# cSLIM-SA_display.net
KiCad netlist of a schematic drawn in Altium Designer
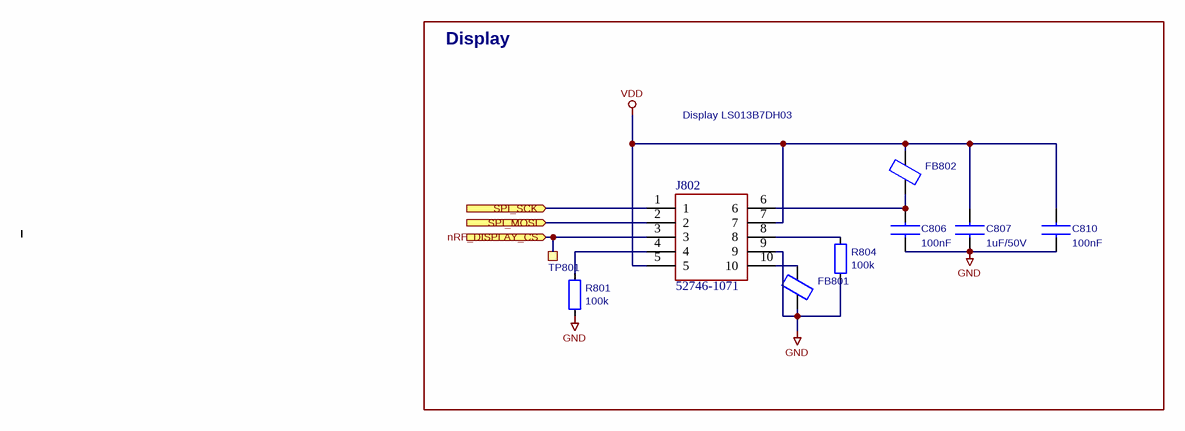
[diagram p0: cSLIM-SA_display.SchDoc]

(export (version "E")
  (design (tool "Eeschema 10.0.6"))
  (components
    (comp (ref "C806")
      (value "100nF")
      (footprint "cSLIM-SA:CAPC1608X90N")
      (description "Capacitor")
      (fields
        (field (name "MANUFACTURER_PART_NUMBER") "06033G104ZAT2A")
        (field (name "MOUSER PART NUMBER") "581-06033G104Z")
      )
      (libsource (lib "cSLIM-SA") (part "C"))
    )
    (comp (ref "C807")
      (value "1uF/50V")
      (footprint "cSLIM-SA:CAPC1608X90N")
      (description "Capacitor")
      (fields
        (field (name "MANUFACTURER_PART_NUMBER") "06033G104ZAT2A")
        (field (name "MOUSER PART NUMBER") "581-06033G104Z")
      )
      (libsource (lib "cSLIM-SA") (part "C"))
    )
    (comp (ref "C810")
      (value "100nF")
      (footprint "cSLIM-SA:CAPC1608X90N")
      (description "Capacitor")
      (fields
        (field (name "MANUFACTURER_PART_NUMBER") "06033G104ZAT2A")
        (field (name "MOUSER PART NUMBER") "581-06033G104Z")
      )
      (libsource (lib "cSLIM-SA") (part "C"))
    )
    (comp (ref "FB801")
      (value "Ferrite_Bead")
      (footprint "CAPC1608X90N")
      (libsource (lib "cSLIM-SA") (part "Ferrite_Bead"))
    )
    (comp (ref "FB802")
      (value "Ferrite_Bead")
      (footprint "CAPC1608X90N")
      (libsource (lib "cSLIM-SA") (part "Ferrite_Bead"))
    )
    (comp (ref "J802")
      (value "52746-1071")
      (footprint "cSLIM-SA:52746-1071")
      (description "Connector")
      (fields (field (name "MOUSER PART NUMBER") "538-52746-1071"))
      (libsource (lib "cSLIM-SA") (part "52746-1071"))
    )
    (comp (ref "R801") (value "100k") (footprint "RESC1608X55N") (libsource (lib "cSLIM-SA") (part "R")))
    (comp (ref "R804") (value "100k") (footprint "RESC1608X55N") (libsource (lib "cSLIM-SA") (part "R")))
    (comp (ref "TP801")
      (value "~")
      (footprint "cSLIM-SA:TP_SMD_Ø1.0mm")
      (libsource (lib "cSLIM-SA") (part "TP"))
    )
  )
  (nets
    (net (code "1") (name "/SPI_MOSI") (class "Default")
      (node (ref "J802") (pin "2") (pinfunction "2_2") (pintype "passive"))
    )
    (net (code "2") (name "/SPI_SCK") (class "Default")
      (node (ref "J802") (pin "1") (pinfunction "1_1") (pintype "passive"))
    )
    (net (code "3") (name "/nRF_DISPLAY_CS") (class "Default")
      (node (ref "J802") (pin "3") (pinfunction "3_3") (pintype "passive"))
      (node (ref "TP801") (pin "1") (pinfunction "1_1") (pintype "passive"))
    )
    (net (code "4") (name "GND") (class "Default")
      (node (ref "C806") (pin "2") (pinfunction "2_2") (pintype "passive"))
      (node (ref "C807") (pin "2") (pinfunction "2_2") (pintype "passive"))
      (node (ref "C810") (pin "2") (pinfunction "2_2") (pintype "passive"))
      (node (ref "FB801") (pin "2") (pinfunction "2_2") (pintype "passive"))
      (node (ref "J802") (pin "9") (pinfunction "9_9") (pintype "passive"))
      (node (ref "R801") (pin "2") (pinfunction "2_2") (pintype "passive"))
      (node (ref "R804") (pin "2") (pinfunction "2_2") (pintype "passive"))
    )
    (net (code "5") (name "Net-(C806-Pad1)") (class "Default")
      (node (ref "C806") (pin "1") (pinfunction "1_1") (pintype "passive"))
      (node (ref "FB802") (pin "2") (pinfunction "2_2") (pintype "passive"))
      (node (ref "J802") (pin "6") (pinfunction "6_6") (pintype "passive"))
    )
    (net (code "6") (name "Net-(FB801-Pad1)") (class "Default")
      (node (ref "FB801") (pin "1") (pinfunction "1_1") (pintype "passive"))
      (node (ref "J802") (pin "10") (pinfunction "10_10") (pintype "passive"))
    )
    (net (code "7") (name "Net-(J802-Pad4)") (class "Default")
      (node (ref "J802") (pin "4") (pinfunction "4_4") (pintype "passive"))
      (node (ref "R801") (pin "1") (pinfunction "1_1") (pintype "passive"))
    )
    (net (code "8") (name "Net-(J802-Pad8)") (class "Default")
      (node (ref "J802") (pin "8") (pinfunction "8_8") (pintype "passive"))
      (node (ref "R804") (pin "1") (pinfunction "1_1") (pintype "passive"))
    )
    (net (code "9") (name "VDD") (class "Default")
      (node (ref "C807") (pin "1") (pinfunction "1_1") (pintype "passive"))
      (node (ref "C810") (pin "1") (pinfunction "1_1") (pintype "passive"))
      (node (ref "FB802") (pin "1") (pinfunction "1_1") (pintype "passive"))
      (node (ref "J802") (pin "5") (pinfunction "5_5") (pintype "passive"))
      (node (ref "J802") (pin "7") (pinfunction "7_7") (pintype "passive"))
    )
  )
)
